# amp-LNA-UHF-TQP3M9036.net
KiCad netlist of a schematic drawn in EAGLE
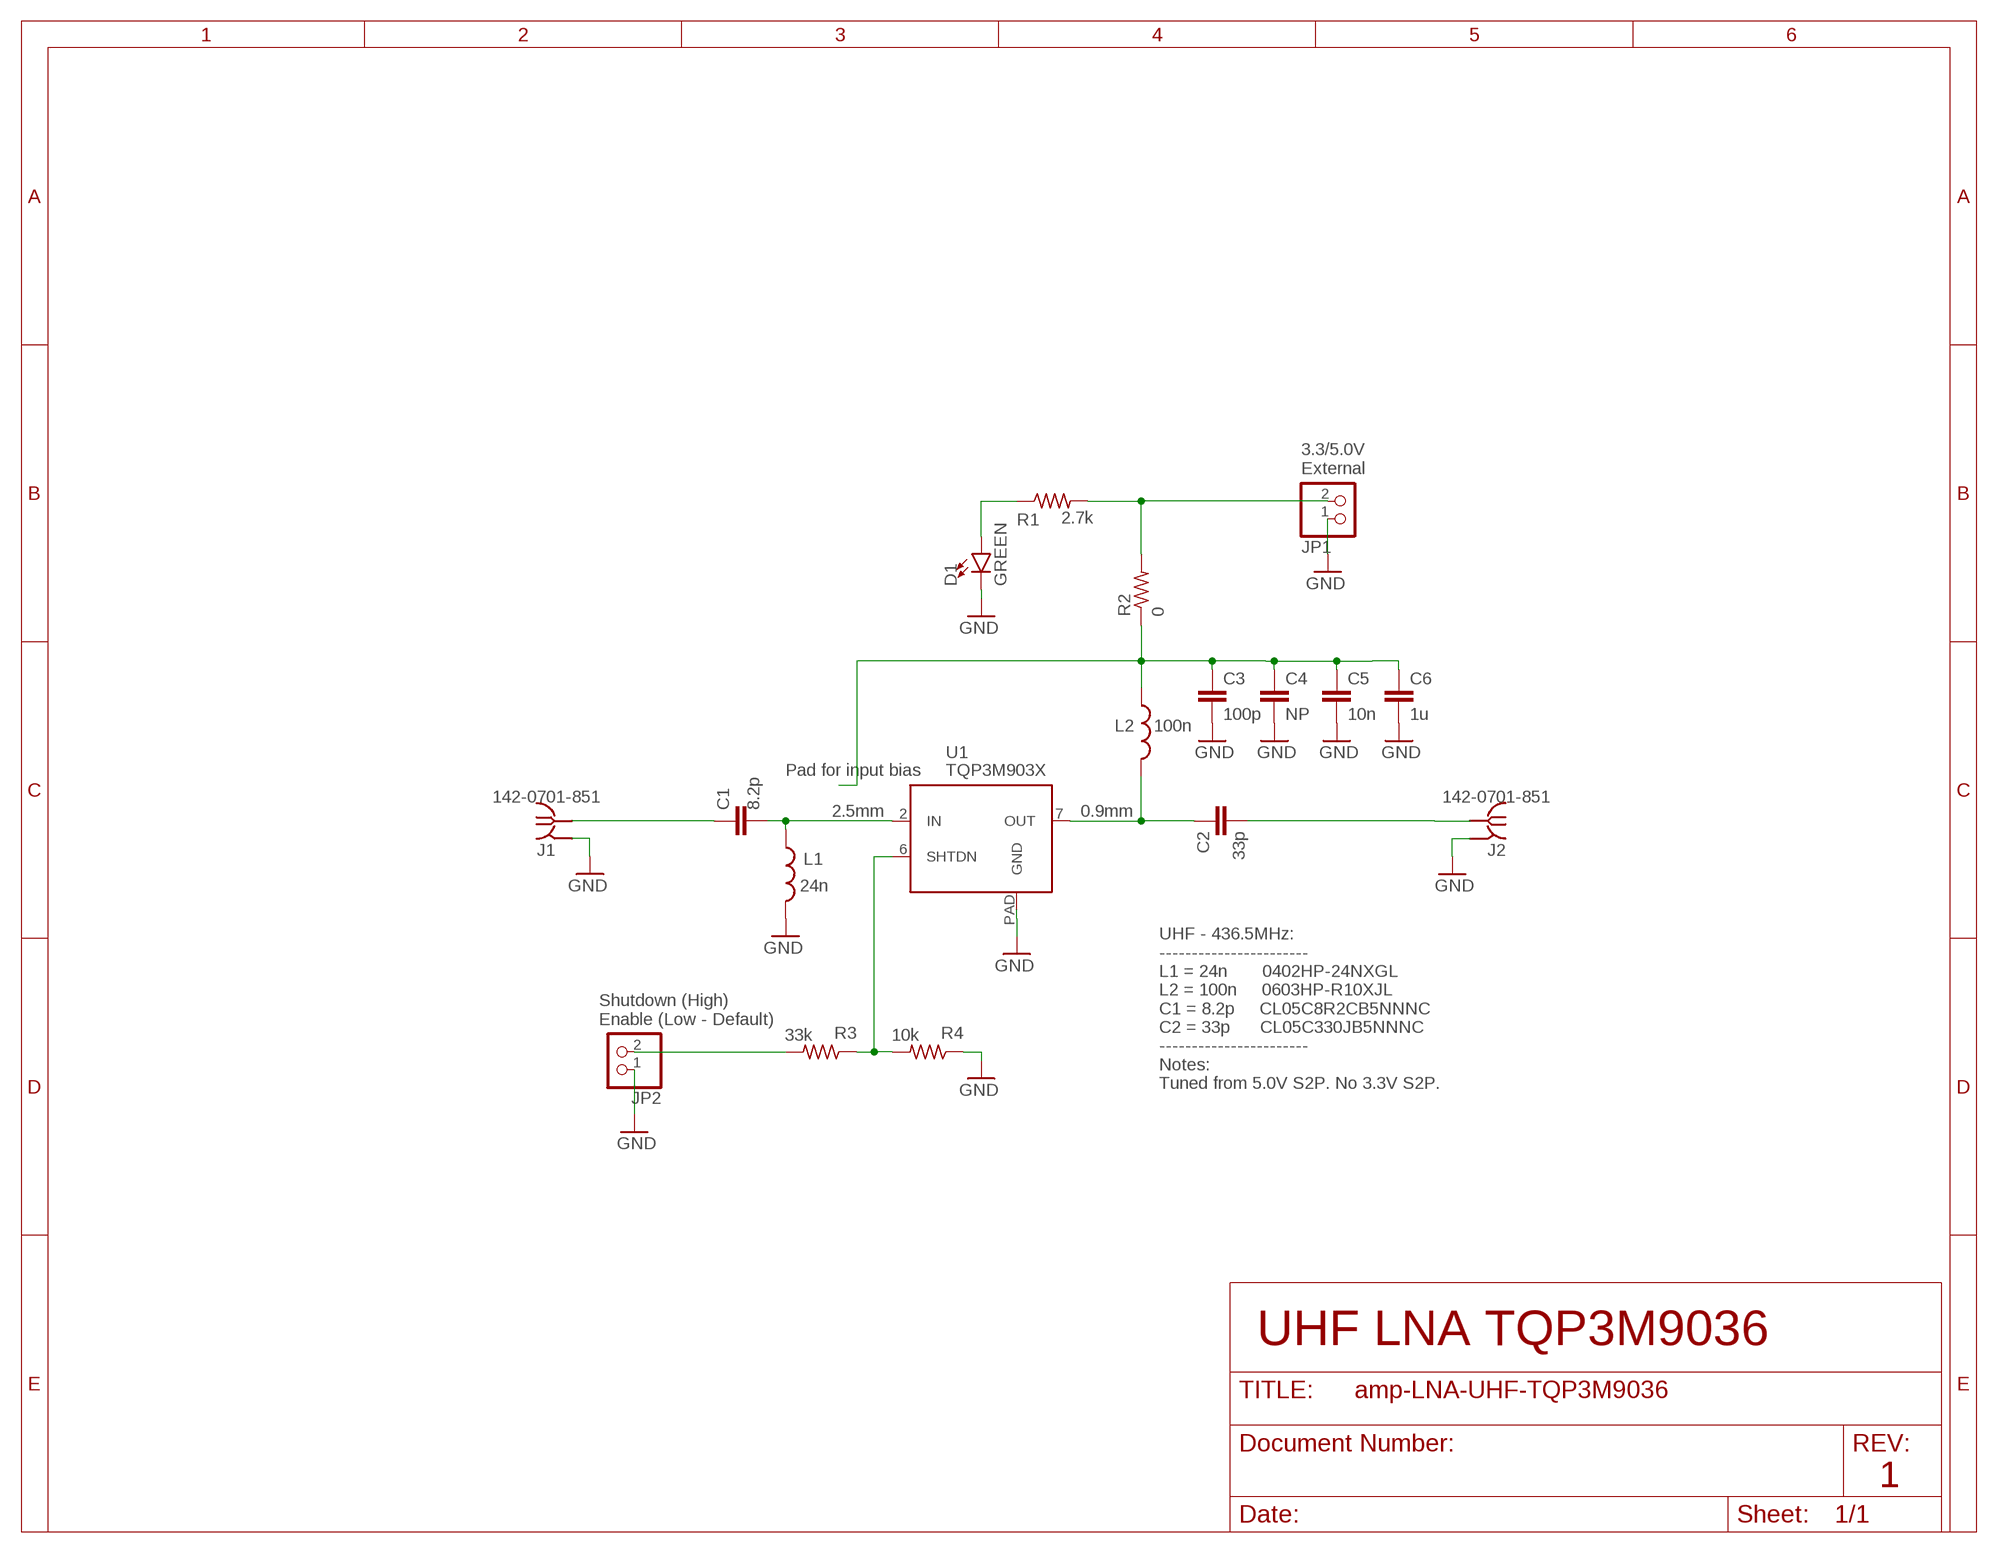
[diagram p0: schematic, sheet 1]

(export (version "E")
  (design (tool "Eeschema 10.0.6"))
  (components
    (comp (ref "C1")
      (value "8.2p")
      (footprint "eagle-import:.0402-C-NOSILK")
      (libsource (lib "eagle-import") (part "C-EU0402-C-NOSILK"))
    )
    (comp (ref "C2")
      (value "33p")
      (footprint "eagle-import:.0402-C-NOSILK")
      (libsource (lib "eagle-import") (part "C-EU0402-C-NOSILK"))
    )
    (comp (ref "C3")
      (value "100p")
      (footprint "eagle-import:.0603-B-NOSILK")
      (libsource (lib "eagle-import") (part "C-EU0603-B-NOSILK"))
    )
    (comp (ref "C4")
      (value "NP")
      (footprint "eagle-import:.0603-B-NOSILK")
      (libsource (lib "eagle-import") (part "C-EU0603-B-NOSILK"))
    )
    (comp (ref "C5")
      (value "10n")
      (footprint "eagle-import:.0603-B-NOSILK")
      (libsource (lib "eagle-import") (part "C-EU0603-B-NOSILK"))
    )
    (comp (ref "C6")
      (value "1u")
      (footprint "eagle-import:.0603-B-NOSILK")
      (libsource (lib "eagle-import") (part "C-EU0603-B-NOSILK"))
    )
    (comp (ref "D1")
      (value "GREEN")
      (footprint "eagle-import:LED-0603")
      (libsource (lib "eagle-import") (part "LED-GREEN0603"))
    )
    (comp (ref "J1")
      (value "142-0701-851")
      (footprint "eagle-import:142-0701-851")
      (libsource (lib "eagle-import") (part "142-0701-851"))
    )
    (comp (ref "J2")
      (value "142-0701-851")
      (footprint "eagle-import:142-0701-851")
      (libsource (lib "eagle-import") (part "142-0701-851"))
    )
    (comp (ref "JP1")
      (value "PINHD-1X2")
      (footprint "eagle-import:1X02")
      (libsource (lib "eagle-import") (part "PINHD-1X2"))
    )
    (comp (ref "JP2")
      (value "PINHD-1X2")
      (footprint "eagle-import:1X02")
      (libsource (lib "eagle-import") (part "PINHD-1X2"))
    )
    (comp (ref "L1")
      (value "24n")
      (footprint "eagle-import:.0402-C-NOSILK")
      (libsource (lib "eagle-import") (part "L-US0402-C-NOSILK"))
    )
    (comp (ref "L2")
      (value "100n")
      (footprint "eagle-import:.0603-C-NOSILK")
      (libsource (lib "eagle-import") (part "L-US0603-C-NOSILK"))
    )
    (comp (ref "R1")
      (value "2.7k")
      (footprint "eagle-import:.0603-B-NOSILK")
      (libsource (lib "eagle-import") (part "R-US_0603-B-NOSILK"))
    )
    (comp (ref "R2")
      (value "0")
      (footprint "eagle-import:.0603-B-NOSILK")
      (libsource (lib "eagle-import") (part "R-US_0603-B-NOSILK"))
    )
    (comp (ref "R3")
      (value "33k")
      (footprint "eagle-import:.0603-B-NOSILK")
      (libsource (lib "eagle-import") (part "R-US_0603-B-NOSILK"))
    )
    (comp (ref "R4")
      (value "10k")
      (footprint "eagle-import:.0603-B-NOSILK")
      (libsource (lib "eagle-import") (part "R-US_0603-B-NOSILK"))
    )
    (comp (ref "U1")
      (value "TQP3M903X")
      (footprint "eagle-import:DFN8-2X2-WITH-PAD")
      (libsource (lib "eagle-import") (part "TQP3M903X"))
    )
  )
  (nets
    (net (code "1") (name "GND") (class "Default")
      (node (ref "C3") (pin "2") (pinfunction "2_2") (pintype "passive"))
      (node (ref "C4") (pin "2") (pinfunction "2_2") (pintype "passive"))
      (node (ref "C5") (pin "2") (pinfunction "2_2") (pintype "passive"))
      (node (ref "C6") (pin "2") (pinfunction "2_2") (pintype "passive"))
      (node (ref "D1") (pin "C") (pinfunction "C_C") (pintype "passive"))
      (node (ref "J1") (pin "GND1") (pinfunction "GND_GND1") (pintype "bidirectional"))
      (node (ref "J1") (pin "GND2") (pinfunction "GND_GND2") (pintype "bidirectional"))
      (node (ref "J1") (pin "GND3") (pinfunction "GND_GND3") (pintype "bidirectional"))
      (node (ref "J1") (pin "GND4") (pinfunction "GND_GND4") (pintype "bidirectional"))
      (node (ref "J2") (pin "GND1") (pinfunction "GND_GND1") (pintype "bidirectional"))
      (node (ref "J2") (pin "GND2") (pinfunction "GND_GND2") (pintype "bidirectional"))
      (node (ref "J2") (pin "GND3") (pinfunction "GND_GND3") (pintype "bidirectional"))
      (node (ref "J2") (pin "GND4") (pinfunction "GND_GND4") (pintype "bidirectional"))
      (node (ref "JP1") (pin "1") (pinfunction "1_1") (pintype "passive"))
      (node (ref "JP2") (pin "1") (pinfunction "1_1") (pintype "passive"))
      (node (ref "L1") (pin "2") (pinfunction "2_2") (pintype "passive"))
      (node (ref "R4") (pin "1") (pinfunction "1_1") (pintype "passive"))
      (node (ref "U1") (pin "PAD") (pinfunction "GND_PAD") (pintype "power_in"))
    )
    (net (code "2") (name "Net-(C3-Pad1)") (class "Default")
      (node (ref "C3") (pin "1") (pinfunction "1_1") (pintype "passive"))
      (node (ref "C4") (pin "1") (pinfunction "1_1") (pintype "passive"))
      (node (ref "C5") (pin "1") (pinfunction "1_1") (pintype "passive"))
      (node (ref "C6") (pin "1") (pinfunction "1_1") (pintype "passive"))
      (node (ref "L2") (pin "1") (pinfunction "1_1") (pintype "passive"))
      (node (ref "R2") (pin "1") (pinfunction "1_1") (pintype "passive"))
    )
    (net (code "3") (name "Net-(D1-PadA)") (class "Default")
      (node (ref "D1") (pin "A") (pinfunction "A_A") (pintype "passive"))
      (node (ref "R1") (pin "1") (pinfunction "1_1") (pintype "passive"))
    )
    (net (code "4") (name "Net-(J1-RF)") (class "Default")
      (node (ref "C1") (pin "1") (pinfunction "1_1") (pintype "passive"))
      (node (ref "J1") (pin "RF1") (pinfunction "RF_RF1") (pintype "bidirectional"))
    )
    (net (code "5") (name "Net-(J2-RF)") (class "Default")
      (node (ref "C2") (pin "2") (pinfunction "2_2") (pintype "passive"))
      (node (ref "J2") (pin "RF1") (pinfunction "RF_RF1") (pintype "bidirectional"))
    )
    (net (code "6") (name "Net-(JP1-Pad2)") (class "Default")
      (node (ref "JP1") (pin "2") (pinfunction "2_2") (pintype "passive"))
      (node (ref "R1") (pin "2") (pinfunction "2_2") (pintype "passive"))
      (node (ref "R2") (pin "2") (pinfunction "2_2") (pintype "passive"))
    )
    (net (code "7") (name "Net-(JP2-Pad2)") (class "Default")
      (node (ref "JP2") (pin "2") (pinfunction "2_2") (pintype "passive"))
      (node (ref "R3") (pin "2") (pinfunction "2_2") (pintype "passive"))
    )
    (net (code "8") (name "Net-(U1-IN)") (class "Default")
      (node (ref "C1") (pin "2") (pinfunction "2_2") (pintype "passive"))
      (node (ref "L1") (pin "1") (pinfunction "1_1") (pintype "passive"))
      (node (ref "U1") (pin "2") (pinfunction "IN_2") (pintype "input"))
    )
    (net (code "9") (name "Net-(U1-OUT)") (class "Default")
      (node (ref "C2") (pin "1") (pinfunction "1_1") (pintype "passive"))
      (node (ref "L2") (pin "2") (pinfunction "2_2") (pintype "passive"))
      (node (ref "U1") (pin "7") (pinfunction "OUT_7") (pintype "output"))
    )
    (net (code "10") (name "Net-(U1-SHTDN)") (class "Default")
      (node (ref "R3") (pin "1") (pinfunction "1_1") (pintype "passive"))
      (node (ref "R4") (pin "2") (pinfunction "2_2") (pintype "passive"))
      (node (ref "U1") (pin "6") (pinfunction "SHTDN_6") (pintype "input"))
    )
  )
)
